# Sheet_3.net
KiCad netlist of a schematic drawn in EasyEDA
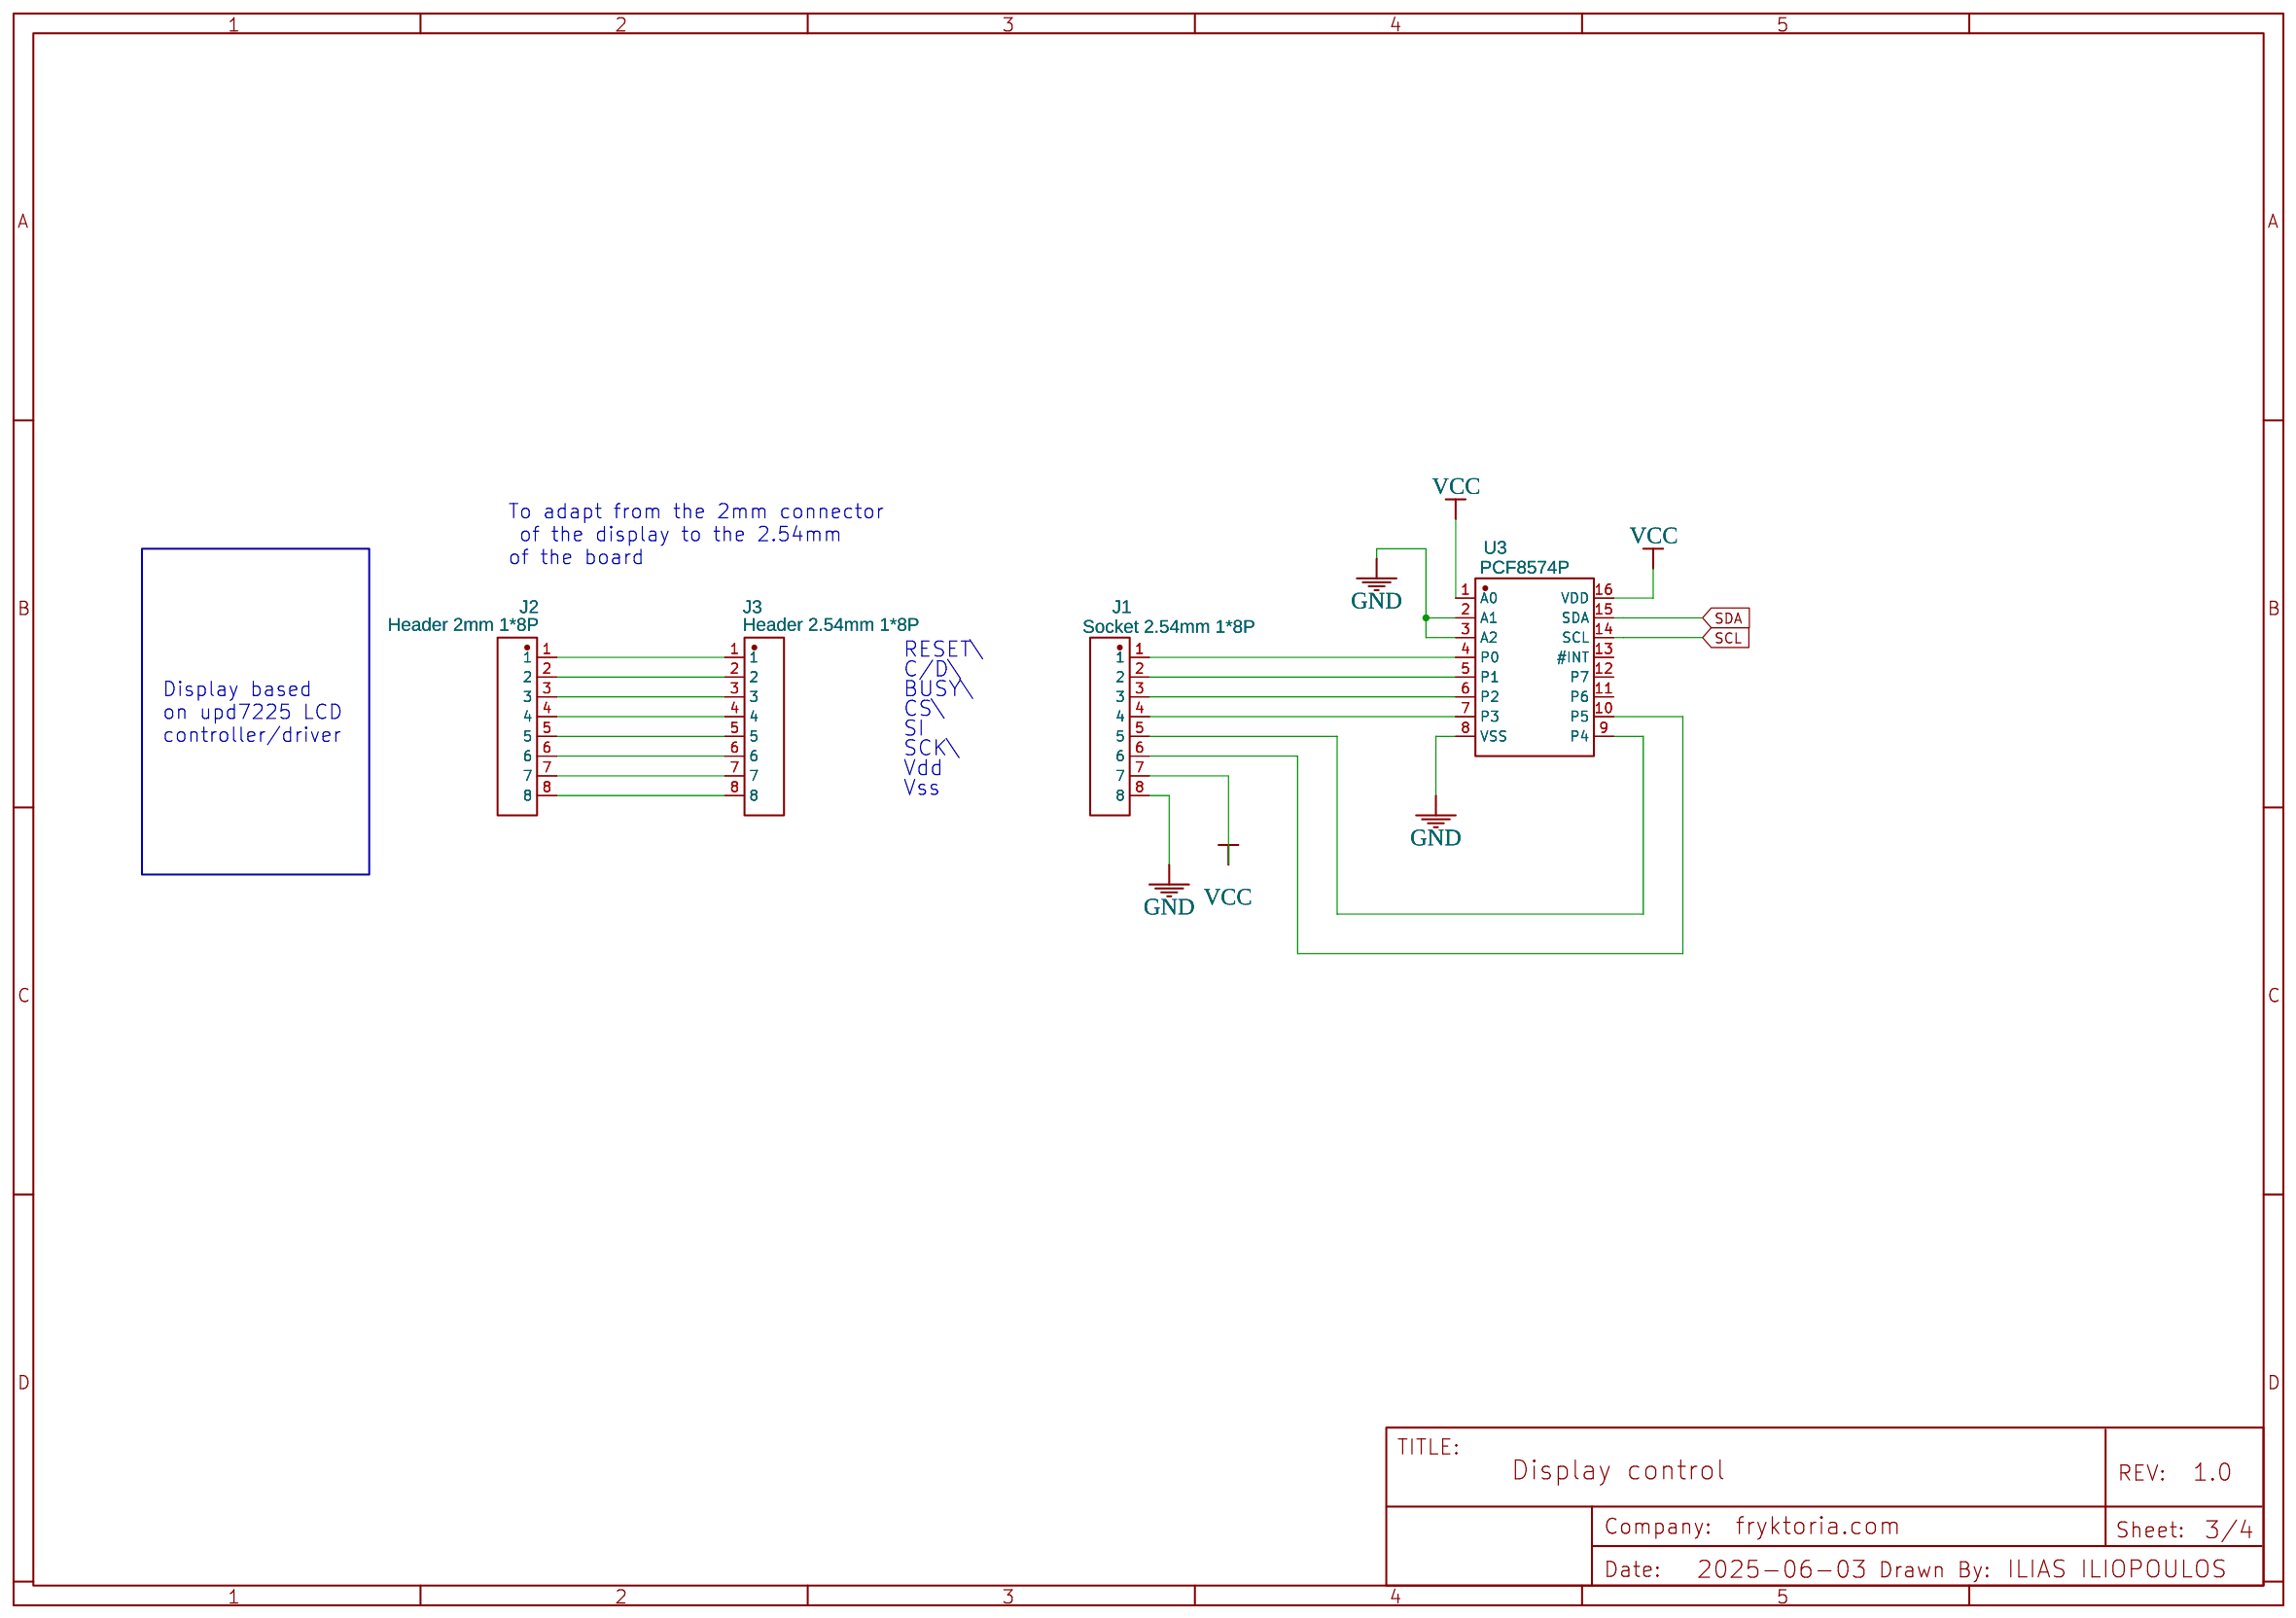
[diagram p0: schematic sheet]

(export (version "E")
  (design (tool "Eeschema 10.0.6"))
  (components
    (comp (ref "J1")
      (value "Socket 2.54mm 1*8P")
      (fields (field (name "Manufacturer Part") "Header2.54mm 1*8P") (field (name "Manufacturer") "ReliaPro"))
      (libsource (lib "") (part "Header2.54mm 1*8P"))
    )
    (comp (ref "J2")
      (value "Header 2mm 1*8P")
      (fields (field (name "Manufacturer Part") "Header2.54mm 1*8P") (field (name "Manufacturer") "ReliaPro"))
      (libsource (lib "") (part "Header2.54mm 1*8P"))
    )
    (comp (ref "J3")
      (value "Header 2.54mm 1*8P")
      (fields (field (name "Manufacturer Part") "Header2.54mm 1*8P") (field (name "Manufacturer") "ReliaPro"))
      (libsource (lib "") (part "Header2.54mm 1*8P_1"))
    )
    (comp (ref "U3")
      (value "PCF8574P")
      (fields (field (name "Manufacturer") "HGSEMI(华冠)"))
      (libsource (lib "") (part "PCF8574P"))
    )
  )
  (nets
    (net (code "1") (name "GND") (class "Default")
      (node (ref "J1") (pin "8") (pinfunction "8_8") (pintype "unspecified"))
      (node (ref "U3") (pin "2") (pinfunction "A1_2") (pintype "unspecified"))
      (node (ref "U3") (pin "3") (pinfunction "A2_3") (pintype "unspecified"))
      (node (ref "U3") (pin "8") (pinfunction "VSS_8") (pintype "unspecified"))
    )
    (net (code "2") (name "Net-(J2-Pad1)") (class "Default")
      (node (ref "J2") (pin "1") (pinfunction "1_1") (pintype "unspecified"))
      (node (ref "J3") (pin "1") (pinfunction "1_1") (pintype "unspecified"))
    )
    (net (code "3") (name "Net-(J2-Pad2)") (class "Default")
      (node (ref "J2") (pin "2") (pinfunction "2_2") (pintype "unspecified"))
      (node (ref "J3") (pin "2") (pinfunction "2_2") (pintype "unspecified"))
    )
    (net (code "4") (name "Net-(J2-Pad3)") (class "Default")
      (node (ref "J2") (pin "3") (pinfunction "3_3") (pintype "unspecified"))
      (node (ref "J3") (pin "3") (pinfunction "3_3") (pintype "unspecified"))
    )
    (net (code "5") (name "Net-(J2-Pad4)") (class "Default")
      (node (ref "J2") (pin "4") (pinfunction "4_4") (pintype "unspecified"))
      (node (ref "J3") (pin "4") (pinfunction "4_4") (pintype "unspecified"))
    )
    (net (code "6") (name "Net-(J2-Pad5)") (class "Default")
      (node (ref "J2") (pin "5") (pinfunction "5_5") (pintype "unspecified"))
      (node (ref "J3") (pin "5") (pinfunction "5_5") (pintype "unspecified"))
    )
    (net (code "7") (name "Net-(J2-Pad6)") (class "Default")
      (node (ref "J2") (pin "6") (pinfunction "6_6") (pintype "unspecified"))
      (node (ref "J3") (pin "6") (pinfunction "6_6") (pintype "unspecified"))
    )
    (net (code "8") (name "Net-(J2-Pad7)") (class "Default")
      (node (ref "J2") (pin "7") (pinfunction "7_7") (pintype "unspecified"))
      (node (ref "J3") (pin "7") (pinfunction "7_7") (pintype "unspecified"))
    )
    (net (code "9") (name "Net-(J2-Pad8)") (class "Default")
      (node (ref "J2") (pin "8") (pinfunction "8_8") (pintype "unspecified"))
      (node (ref "J3") (pin "8") (pinfunction "8_8") (pintype "unspecified"))
    )
    (net (code "10") (name "Net-(U3-P0)") (class "Default")
      (node (ref "J1") (pin "1") (pinfunction "1_1") (pintype "unspecified"))
      (node (ref "U3") (pin "4") (pinfunction "P0_4") (pintype "unspecified"))
    )
    (net (code "11") (name "Net-(U3-P1)") (class "Default")
      (node (ref "J1") (pin "2") (pinfunction "2_2") (pintype "unspecified"))
      (node (ref "U3") (pin "5") (pinfunction "P1_5") (pintype "unspecified"))
    )
    (net (code "12") (name "Net-(U3-P2)") (class "Default")
      (node (ref "J1") (pin "3") (pinfunction "3_3") (pintype "unspecified"))
      (node (ref "U3") (pin "6") (pinfunction "P2_6") (pintype "unspecified"))
    )
    (net (code "13") (name "Net-(U3-P3)") (class "Default")
      (node (ref "J1") (pin "4") (pinfunction "4_4") (pintype "unspecified"))
      (node (ref "U3") (pin "7") (pinfunction "P3_7") (pintype "unspecified"))
    )
    (net (code "14") (name "Net-(U3-P4)") (class "Default")
      (node (ref "J1") (pin "5") (pinfunction "5_5") (pintype "unspecified"))
      (node (ref "U3") (pin "9") (pinfunction "P4_9") (pintype "unspecified"))
    )
    (net (code "15") (name "Net-(U3-P5)") (class "Default")
      (node (ref "J1") (pin "6") (pinfunction "6_6") (pintype "unspecified"))
      (node (ref "U3") (pin "10") (pinfunction "P5_10") (pintype "unspecified"))
    )
    (net (code "16") (name "SCL") (class "Default")
      (node (ref "U3") (pin "14") (pinfunction "SCL_14") (pintype "unspecified"))
    )
    (net (code "17") (name "SDA") (class "Default")
      (node (ref "U3") (pin "15") (pinfunction "SDA_15") (pintype "unspecified"))
    )
    (net (code "18") (name "VCC") (class "Default")
      (node (ref "J1") (pin "7") (pinfunction "7_7") (pintype "unspecified"))
      (node (ref "U3") (pin "1") (pinfunction "A0_1") (pintype "unspecified"))
      (node (ref "U3") (pin "16") (pinfunction "VDD_16") (pintype "unspecified"))
    )
    (net (code "19") (name "unconnected-(U3-#INT-Pad13)") (class "Default")
      (node (ref "U3") (pin "13") (pinfunction "#INT_13") (pintype "unspecified"))
    )
    (net (code "20") (name "unconnected-(U3-P6-Pad11)") (class "Default")
      (node (ref "U3") (pin "11") (pinfunction "P6_11") (pintype "unspecified"))
    )
    (net (code "21") (name "unconnected-(U3-P7-Pad12)") (class "Default")
      (node (ref "U3") (pin "12") (pinfunction "P7_12") (pintype "unspecified"))
    )
  )
)
